# lora_esp.net
KiCad netlist of a schematic drawn in EAGLE
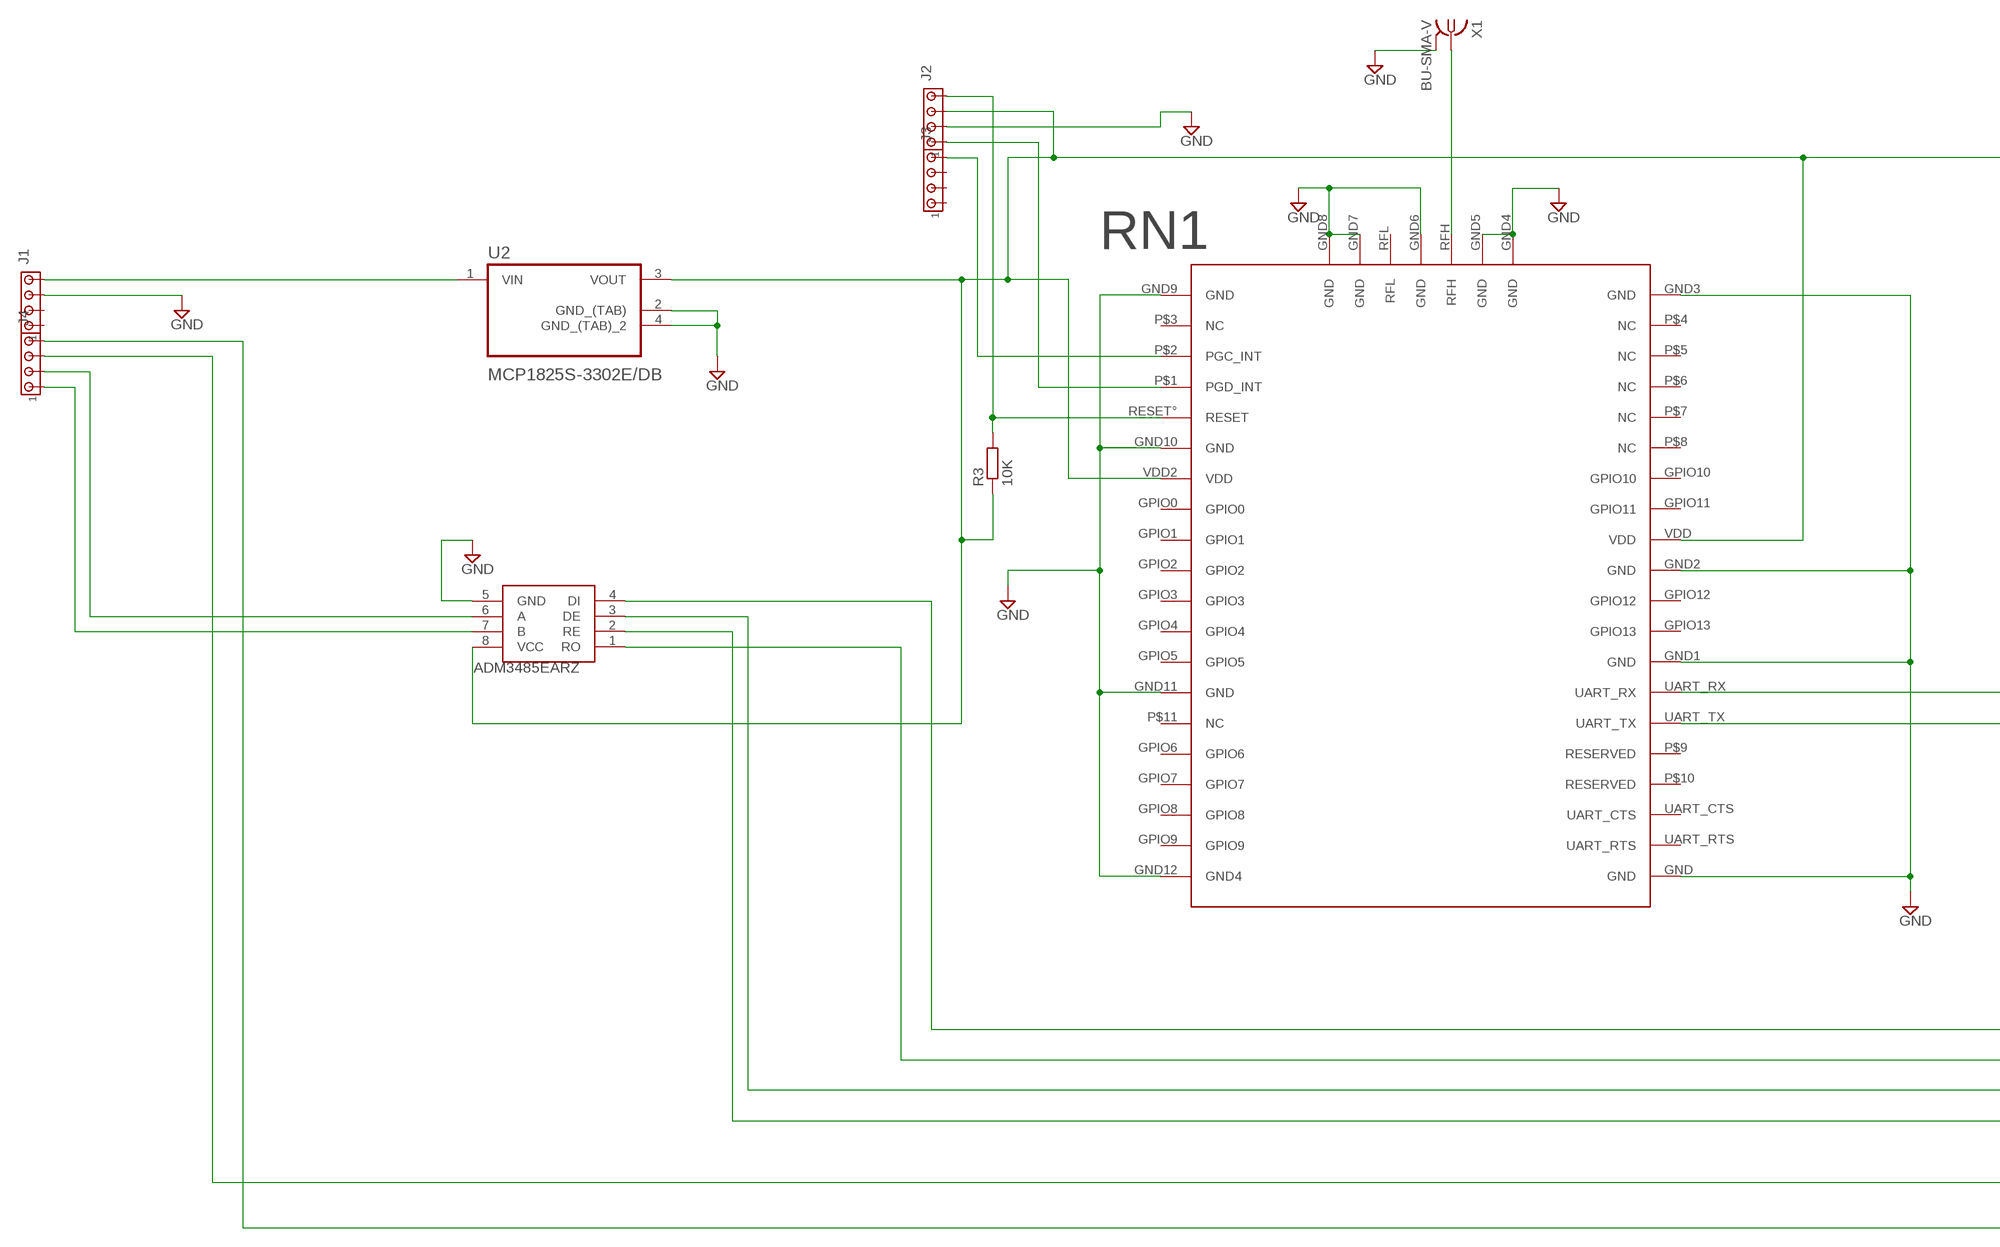
[diagram p0: schematic, sheet 1, part 1 of 2]
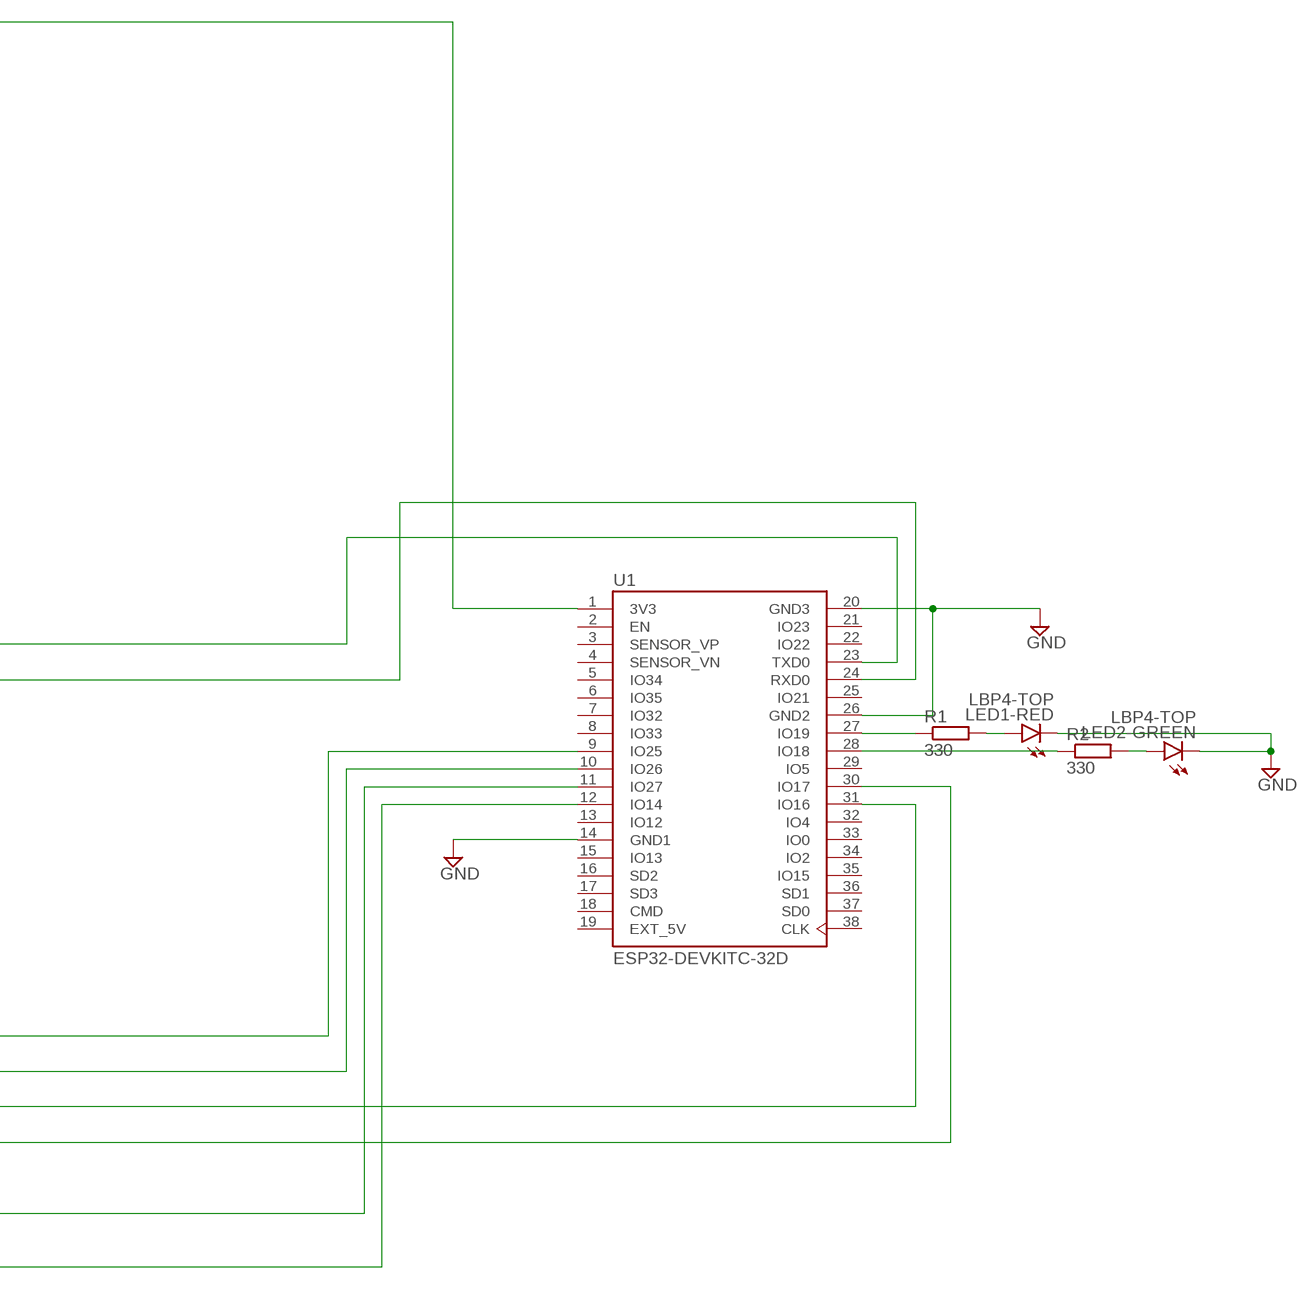
[diagram p1: schematic, sheet 1, part 2 of 2]

(export (version "E")
  (design (tool "Eeschema 10.0.6"))
  (components
    (comp (ref "ADM3485EARZ")
      (value "AMD3485E")
      (footprint "eagle-import:AMD3485E")
      (libsource (lib "eagle-import") (part "AMD3485E"))
    )
    (comp (ref "J1")
      (value "MTA04-100")
      (footprint "eagle-import:10X04MTA")
      (libsource (lib "eagle-import") (part "MTA04-100"))
    )
    (comp (ref "J2")
      (value "MTA04-100")
      (footprint "eagle-import:10X04MTA")
      (libsource (lib "eagle-import") (part "MTA04-100"))
    )
    (comp (ref "J3")
      (value "MTA04-100")
      (footprint "eagle-import:10X04MTA")
      (libsource (lib "eagle-import") (part "MTA04-100"))
    )
    (comp (ref "J4")
      (value "MTA04-100")
      (footprint "eagle-import:10X04MTA")
      (libsource (lib "eagle-import") (part "MTA04-100"))
    )
    (comp (ref "LED1-RED")
      (value "LBP4-TOP")
      (footprint "eagle-import:P47F-TOP")
      (libsource (lib "eagle-import") (part "P4-TOPLB"))
    )
    (comp (ref "LED2-GREEN")
      (value "LBP4-TOP")
      (footprint "eagle-import:P47F-TOP")
      (libsource (lib "eagle-import") (part "P4-TOPLB"))
    )
    (comp (ref "R1")
      (value "330")
      (footprint "eagle-import:0204_5")
      (libsource (lib "eagle-import") (part "R-EU_0204/5"))
    )
    (comp (ref "R2")
      (value "330")
      (footprint "eagle-import:0204_5")
      (libsource (lib "eagle-import") (part "R-EU_0204/5"))
    )
    (comp (ref "R3")
      (value "10K")
      (footprint "eagle-import:0204_5")
      (libsource (lib "eagle-import") (part "R-EU_0204/5"))
    )
    (comp (ref "RN1")
      (value "NEW_RN2483")
      (footprint "eagle-import:NEW_RN2483")
      (libsource (lib "eagle-import") (part "NEW_RN2483"))
    )
    (comp (ref "U1")
      (value "ESP32-DEVKITC-32D")
      (footprint "eagle-import:MODULE_ESP32-DEVKITC-32D")
      (fields (field (name "MF") "Espressif Systems"))
      (libsource (lib "eagle-import") (part "ESP32-DEVKITC-32D"))
    )
    (comp (ref "U2")
      (value "MCP1825S-3302E/DB")
      (footprint "eagle-import:SOT230P700X180-4N")
      (fields (field (name "MF") "Microchip"))
      (libsource (lib "eagle-import") (part "MCP1825S-3302E/DB"))
    )
    (comp (ref "X1")
      (value "BU-SMA-V")
      (footprint "eagle-import:BU-SMA-V")
      (libsource (lib "eagle-import") (part "BU-SMA-V"))
    )
  )
  (nets
    (net (code "1") (name "/EXT_5V") (class "Default")
      (node (ref "U1") (pin "19") (pinfunction "EXT_5V_19") (pintype "power_in"))
    )
    (net (code "2") (name "GND") (class "Default")
      (node (ref "ADM3485EARZ") (pin "5") (pinfunction "GND_5") (pintype "bidirectional"))
      (node (ref "J1") (pin "3") (pinfunction "3_3") (pintype "passive"))
      (node (ref "J2") (pin "2") (pinfunction "2_2") (pintype "passive"))
      (node (ref "LED1-RED") (pin "C") (pinfunction "C_C") (pintype "passive"))
      (node (ref "LED2-GREEN") (pin "C") (pinfunction "C_C") (pintype "passive"))
      (node (ref "RN1") (pin "GND") (pinfunction "GND_GND") (pintype "bidirectional"))
      (node (ref "RN1") (pin "GND1") (pinfunction "GND_GND1") (pintype "bidirectional"))
      (node (ref "RN1") (pin "GND10") (pinfunction "GND_GND10") (pintype "bidirectional"))
      (node (ref "RN1") (pin "GND11") (pinfunction "GND_GND11") (pintype "bidirectional"))
      (node (ref "RN1") (pin "GND12") (pinfunction "GND4_GND12") (pintype "bidirectional"))
      (node (ref "RN1") (pin "GND2") (pinfunction "GND_GND2") (pintype "bidirectional"))
      (node (ref "RN1") (pin "GND3") (pinfunction "GND_GND3") (pintype "bidirectional"))
      (node (ref "RN1") (pin "GND4") (pinfunction "GND_GND4") (pintype "bidirectional"))
      (node (ref "RN1") (pin "GND5") (pinfunction "GND_GND5") (pintype "bidirectional"))
      (node (ref "RN1") (pin "GND6") (pinfunction "GND_GND6") (pintype "bidirectional"))
      (node (ref "RN1") (pin "GND7") (pinfunction "GND_GND7") (pintype "bidirectional"))
      (node (ref "RN1") (pin "GND8") (pinfunction "GND_GND8") (pintype "bidirectional"))
      (node (ref "RN1") (pin "GND9") (pinfunction "GND_GND9") (pintype "bidirectional"))
      (node (ref "U1") (pin "14") (pinfunction "GND1_14") (pintype "power_in"))
      (node (ref "U1") (pin "20") (pinfunction "GND3_20") (pintype "power_in"))
      (node (ref "U1") (pin "26") (pinfunction "GND2_26") (pintype "power_in"))
      (node (ref "U2") (pin "2") (pinfunction "GND_(TAB)_2") (pintype "power_in"))
      (node (ref "U2") (pin "4") (pinfunction "GND_(TAB)_2_4") (pintype "power_in"))
      (node (ref "X1") (pin "2") (pinfunction "2_2") (pintype "passive"))
      (node (ref "X1") (pin "3") (pinfunction "2_3") (pintype "passive"))
      (node (ref "X1") (pin "4") (pinfunction "2_4") (pintype "passive"))
      (node (ref "X1") (pin "5") (pinfunction "2_5") (pintype "passive"))
    )
    (net (code "3") (name "Net-(ADM3485EARZ-A)") (class "Default")
      (node (ref "ADM3485EARZ") (pin "6") (pinfunction "A_6") (pintype "bidirectional"))
      (node (ref "J4") (pin "2") (pinfunction "2_2") (pintype "passive"))
    )
    (net (code "4") (name "Net-(ADM3485EARZ-B)") (class "Default")
      (node (ref "ADM3485EARZ") (pin "7") (pinfunction "B_7") (pintype "bidirectional"))
      (node (ref "J4") (pin "1") (pinfunction "1_1") (pintype "passive"))
    )
    (net (code "5") (name "Net-(ADM3485EARZ-DE)") (class "Default")
      (node (ref "ADM3485EARZ") (pin "3") (pinfunction "DE_3") (pintype "bidirectional"))
      (node (ref "U1") (pin "31") (pinfunction "IO16_31") (pintype "bidirectional"))
    )
    (net (code "6") (name "Net-(ADM3485EARZ-DI)") (class "Default")
      (node (ref "ADM3485EARZ") (pin "4") (pinfunction "DI_4") (pintype "bidirectional"))
      (node (ref "U1") (pin "9") (pinfunction "IO25_9") (pintype "bidirectional"))
    )
    (net (code "7") (name "Net-(ADM3485EARZ-RE)") (class "Default")
      (node (ref "ADM3485EARZ") (pin "2") (pinfunction "RE_2") (pintype "bidirectional"))
      (node (ref "U1") (pin "30") (pinfunction "IO17_30") (pintype "bidirectional"))
    )
    (net (code "8") (name "Net-(ADM3485EARZ-RO)") (class "Default")
      (node (ref "ADM3485EARZ") (pin "1") (pinfunction "RO_1") (pintype "bidirectional"))
      (node (ref "U1") (pin "10") (pinfunction "IO26_10") (pintype "bidirectional"))
    )
    (net (code "9") (name "Net-(ADM3485EARZ-VCC)") (class "Default")
      (node (ref "ADM3485EARZ") (pin "8") (pinfunction "VCC_8") (pintype "bidirectional"))
      (node (ref "J2") (pin "3") (pinfunction "3_3") (pintype "passive"))
      (node (ref "R3") (pin "1") (pinfunction "1_1") (pintype "passive"))
      (node (ref "RN1") (pin "VDD") (pinfunction "VDD_VDD") (pintype "bidirectional"))
      (node (ref "RN1") (pin "VDD2") (pinfunction "VDD_VDD2") (pintype "bidirectional"))
      (node (ref "U1") (pin "1") (pinfunction "3V3_1") (pintype "power_in"))
      (node (ref "U2") (pin "3") (pinfunction "VOUT_3") (pintype "output"))
    )
    (net (code "10") (name "Net-(LED1-RED-PadA)") (class "Default")
      (node (ref "LED1-RED") (pin "A") (pinfunction "A_A") (pintype "passive"))
      (node (ref "R1") (pin "2") (pinfunction "2_2") (pintype "passive"))
    )
    (net (code "11") (name "Net-(LED2-GREEN-PadA)") (class "Default")
      (node (ref "LED2-GREEN") (pin "A") (pinfunction "A_A") (pintype "passive"))
      (node (ref "R2") (pin "2") (pinfunction "2_2") (pintype "passive"))
    )
    (net (code "12") (name "Net-(RN1-PGC_INT)") (class "Default")
      (node (ref "J3") (pin "4") (pinfunction "4_4") (pintype "passive"))
      (node (ref "RN1") (pin "P$2") (pinfunction "PGC_INT_P$2") (pintype "bidirectional"))
    )
    (net (code "13") (name "Net-(RN1-PGD_INT)") (class "Default")
      (node (ref "J2") (pin "1") (pinfunction "1_1") (pintype "passive"))
      (node (ref "RN1") (pin "P$1") (pinfunction "PGD_INT_P$1") (pintype "bidirectional"))
    )
    (net (code "14") (name "Net-(RN1-PadRFH)") (class "Default")
      (node (ref "RN1") (pin "RFH") (pinfunction "RFH_RFH") (pintype "bidirectional"))
      (node (ref "X1") (pin "1") (pinfunction "1_1") (pintype "passive"))
    )
    (net (code "15") (name "Net-(RN1-RESET)") (class "Default")
      (node (ref "J2") (pin "4") (pinfunction "4_4") (pintype "passive"))
      (node (ref "R3") (pin "2") (pinfunction "2_2") (pintype "passive"))
      (node (ref "RN1") (pin "RESET°") (pinfunction "RESET_RESET°") (pintype "bidirectional"))
    )
    (net (code "16") (name "Net-(U1-IO14)") (class "Default")
      (node (ref "J4") (pin "4") (pinfunction "4_4") (pintype "passive"))
      (node (ref "U1") (pin "12") (pinfunction "IO14_12") (pintype "bidirectional"))
    )
    (net (code "17") (name "Net-(U1-IO18)") (class "Default")
      (node (ref "R2") (pin "1") (pinfunction "1_1") (pintype "passive"))
      (node (ref "U1") (pin "28") (pinfunction "IO18_28") (pintype "bidirectional"))
    )
    (net (code "18") (name "Net-(U1-IO19)") (class "Default")
      (node (ref "R1") (pin "1") (pinfunction "1_1") (pintype "passive"))
      (node (ref "U1") (pin "27") (pinfunction "IO19_27") (pintype "bidirectional"))
    )
    (net (code "19") (name "Net-(U1-IO27)") (class "Default")
      (node (ref "J4") (pin "3") (pinfunction "3_3") (pintype "passive"))
      (node (ref "U1") (pin "11") (pinfunction "IO27_11") (pintype "bidirectional"))
    )
    (net (code "20") (name "Net-(U1-RXD0)") (class "Default")
      (node (ref "RN1") (pin "UART_TX") (pinfunction "UART_TX_UART_TX") (pintype "bidirectional"))
      (node (ref "U1") (pin "24") (pinfunction "RXD0_24") (pintype "input"))
    )
    (net (code "21") (name "Net-(U1-TXD0)") (class "Default")
      (node (ref "RN1") (pin "UART_RX") (pinfunction "UART_RX_UART_RX") (pintype "bidirectional"))
      (node (ref "U1") (pin "23") (pinfunction "TXD0_23") (pintype "output"))
    )
    (net (code "22") (name "Net-(U2-VIN)") (class "Default")
      (node (ref "J1") (pin "4") (pinfunction "4_4") (pintype "passive"))
      (node (ref "U2") (pin "1") (pinfunction "VIN_1") (pintype "input"))
    )
    (net (code "23") (name "unconnected-(J1-Pad1)") (class "Default")
      (node (ref "J1") (pin "1") (pinfunction "1_1") (pintype "passive"))
    )
    (net (code "24") (name "unconnected-(J1-Pad2)") (class "Default")
      (node (ref "J1") (pin "2") (pinfunction "2_2") (pintype "passive"))
    )
    (net (code "25") (name "unconnected-(J3-Pad1)") (class "Default")
      (node (ref "J3") (pin "1") (pinfunction "1_1") (pintype "passive"))
    )
    (net (code "26") (name "unconnected-(J3-Pad2)") (class "Default")
      (node (ref "J3") (pin "2") (pinfunction "2_2") (pintype "passive"))
    )
    (net (code "27") (name "unconnected-(J3-Pad3)") (class "Default")
      (node (ref "J3") (pin "3") (pinfunction "3_3") (pintype "passive"))
    )
    (net (code "28") (name "unconnected-(RN1-NC-PadP$3)") (class "Default")
      (node (ref "RN1") (pin "P$3") (pinfunction "NC_P$3") (pintype "bidirectional"))
    )
    (net (code "29") (name "unconnected-(RN1-NC-PadP$4)") (class "Default")
      (node (ref "RN1") (pin "P$4") (pinfunction "NC_P$4") (pintype "bidirectional"))
    )
    (net (code "30") (name "unconnected-(RN1-NC-PadP$5)") (class "Default")
      (node (ref "RN1") (pin "P$5") (pinfunction "NC_P$5") (pintype "bidirectional"))
    )
    (net (code "31") (name "unconnected-(RN1-NC-PadP$6)") (class "Default")
      (node (ref "RN1") (pin "P$6") (pinfunction "NC_P$6") (pintype "bidirectional"))
    )
    (net (code "32") (name "unconnected-(RN1-NC-PadP$7)") (class "Default")
      (node (ref "RN1") (pin "P$7") (pinfunction "NC_P$7") (pintype "bidirectional"))
    )
    (net (code "33") (name "unconnected-(RN1-NC-PadP$8)") (class "Default")
      (node (ref "RN1") (pin "P$8") (pinfunction "NC_P$8") (pintype "bidirectional"))
    )
    (net (code "34") (name "unconnected-(RN1-NC-PadP$11)") (class "Default")
      (node (ref "RN1") (pin "P$11") (pinfunction "NC_P$11") (pintype "bidirectional"))
    )
    (net (code "35") (name "unconnected-(RN1-PadGPIO0)") (class "Default")
      (node (ref "RN1") (pin "GPIO0") (pinfunction "GPIO0_GPIO0") (pintype "bidirectional"))
    )
    (net (code "36") (name "unconnected-(RN1-PadGPIO1)") (class "Default")
      (node (ref "RN1") (pin "GPIO1") (pinfunction "GPIO1_GPIO1") (pintype "bidirectional"))
    )
    (net (code "37") (name "unconnected-(RN1-PadGPIO2)") (class "Default")
      (node (ref "RN1") (pin "GPIO2") (pinfunction "GPIO2_GPIO2") (pintype "bidirectional"))
    )
    (net (code "38") (name "unconnected-(RN1-PadGPIO3)") (class "Default")
      (node (ref "RN1") (pin "GPIO3") (pinfunction "GPIO3_GPIO3") (pintype "bidirectional"))
    )
    (net (code "39") (name "unconnected-(RN1-PadGPIO4)") (class "Default")
      (node (ref "RN1") (pin "GPIO4") (pinfunction "GPIO4_GPIO4") (pintype "bidirectional"))
    )
    (net (code "40") (name "unconnected-(RN1-PadGPIO5)") (class "Default")
      (node (ref "RN1") (pin "GPIO5") (pinfunction "GPIO5_GPIO5") (pintype "bidirectional"))
    )
    (net (code "41") (name "unconnected-(RN1-PadGPIO6)") (class "Default")
      (node (ref "RN1") (pin "GPIO6") (pinfunction "GPIO6_GPIO6") (pintype "bidirectional"))
    )
    (net (code "42") (name "unconnected-(RN1-PadGPIO7)") (class "Default")
      (node (ref "RN1") (pin "GPIO7") (pinfunction "GPIO7_GPIO7") (pintype "bidirectional"))
    )
    (net (code "43") (name "unconnected-(RN1-PadGPIO8)") (class "Default")
      (node (ref "RN1") (pin "GPIO8") (pinfunction "GPIO8_GPIO8") (pintype "bidirectional"))
    )
    (net (code "44") (name "unconnected-(RN1-PadGPIO9)") (class "Default")
      (node (ref "RN1") (pin "GPIO9") (pinfunction "GPIO9_GPIO9") (pintype "bidirectional"))
    )
    (net (code "45") (name "unconnected-(RN1-PadGPIO10)") (class "Default")
      (node (ref "RN1") (pin "GPIO10") (pinfunction "GPIO10_GPIO10") (pintype "bidirectional"))
    )
    (net (code "46") (name "unconnected-(RN1-PadGPIO11)") (class "Default")
      (node (ref "RN1") (pin "GPIO11") (pinfunction "GPIO11_GPIO11") (pintype "bidirectional"))
    )
    (net (code "47") (name "unconnected-(RN1-PadGPIO12)") (class "Default")
      (node (ref "RN1") (pin "GPIO12") (pinfunction "GPIO12_GPIO12") (pintype "bidirectional"))
    )
    (net (code "48") (name "unconnected-(RN1-PadGPIO13)") (class "Default")
      (node (ref "RN1") (pin "GPIO13") (pinfunction "GPIO13_GPIO13") (pintype "bidirectional"))
    )
    (net (code "49") (name "unconnected-(RN1-PadRFL)") (class "Default")
      (node (ref "RN1") (pin "RFL") (pinfunction "RFL_RFL") (pintype "bidirectional"))
    )
    (net (code "50") (name "unconnected-(RN1-PadUART_CTS)") (class "Default")
      (node (ref "RN1") (pin "UART_CTS") (pinfunction "UART_CTS_UART_CTS") (pintype "bidirectional"))
    )
    (net (code "51") (name "unconnected-(RN1-PadUART_RTS)") (class "Default")
      (node (ref "RN1") (pin "UART_RTS") (pinfunction "UART_RTS_UART_RTS") (pintype "bidirectional"))
    )
    (net (code "52") (name "unconnected-(RN1-RESERVED-PadP$9)") (class "Default")
      (node (ref "RN1") (pin "P$9") (pinfunction "RESERVED_P$9") (pintype "bidirectional"))
    )
    (net (code "53") (name "unconnected-(RN1-RESERVED-PadP$10)") (class "Default")
      (node (ref "RN1") (pin "P$10") (pinfunction "RESERVED_P$10") (pintype "bidirectional"))
    )
    (net (code "54") (name "unconnected-(U1-CLK-Pad38)") (class "Default")
      (node (ref "U1") (pin "38") (pinfunction "CLK_38") (pintype "input"))
    )
    (net (code "55") (name "unconnected-(U1-CMD-Pad18)") (class "Default")
      (node (ref "U1") (pin "18") (pinfunction "CMD_18") (pintype "bidirectional"))
    )
    (net (code "56") (name "unconnected-(U1-EN-Pad2)") (class "Default")
      (node (ref "U1") (pin "2") (pinfunction "EN_2") (pintype "input"))
    )
    (net (code "57") (name "unconnected-(U1-IO0-Pad33)") (class "Default")
      (node (ref "U1") (pin "33") (pinfunction "IO0_33") (pintype "bidirectional"))
    )
    (net (code "58") (name "unconnected-(U1-IO2-Pad34)") (class "Default")
      (node (ref "U1") (pin "34") (pinfunction "IO2_34") (pintype "bidirectional"))
    )
    (net (code "59") (name "unconnected-(U1-IO4-Pad32)") (class "Default")
      (node (ref "U1") (pin "32") (pinfunction "IO4_32") (pintype "bidirectional"))
    )
    (net (code "60") (name "unconnected-(U1-IO5-Pad29)") (class "Default")
      (node (ref "U1") (pin "29") (pinfunction "IO5_29") (pintype "bidirectional"))
    )
    (net (code "61") (name "unconnected-(U1-IO12-Pad13)") (class "Default")
      (node (ref "U1") (pin "13") (pinfunction "IO12_13") (pintype "bidirectional"))
    )
    (net (code "62") (name "unconnected-(U1-IO13-Pad15)") (class "Default")
      (node (ref "U1") (pin "15") (pinfunction "IO13_15") (pintype "bidirectional"))
    )
    (net (code "63") (name "unconnected-(U1-IO15-Pad35)") (class "Default")
      (node (ref "U1") (pin "35") (pinfunction "IO15_35") (pintype "bidirectional"))
    )
    (net (code "64") (name "unconnected-(U1-IO21-Pad25)") (class "Default")
      (node (ref "U1") (pin "25") (pinfunction "IO21_25") (pintype "bidirectional"))
    )
    (net (code "65") (name "unconnected-(U1-IO22-Pad22)") (class "Default")
      (node (ref "U1") (pin "22") (pinfunction "IO22_22") (pintype "bidirectional"))
    )
    (net (code "66") (name "unconnected-(U1-IO23-Pad21)") (class "Default")
      (node (ref "U1") (pin "21") (pinfunction "IO23_21") (pintype "bidirectional"))
    )
    (net (code "67") (name "unconnected-(U1-IO32-Pad7)") (class "Default")
      (node (ref "U1") (pin "7") (pinfunction "IO32_7") (pintype "bidirectional"))
    )
    (net (code "68") (name "unconnected-(U1-IO33-Pad8)") (class "Default")
      (node (ref "U1") (pin "8") (pinfunction "IO33_8") (pintype "bidirectional"))
    )
    (net (code "69") (name "unconnected-(U1-IO34-Pad5)") (class "Default")
      (node (ref "U1") (pin "5") (pinfunction "IO34_5") (pintype "bidirectional"))
    )
    (net (code "70") (name "unconnected-(U1-IO35-Pad6)") (class "Default")
      (node (ref "U1") (pin "6") (pinfunction "IO35_6") (pintype "bidirectional"))
    )
    (net (code "71") (name "unconnected-(U1-SD0-Pad37)") (class "Default")
      (node (ref "U1") (pin "37") (pinfunction "SD0_37") (pintype "bidirectional"))
    )
    (net (code "72") (name "unconnected-(U1-SD1-Pad36)") (class "Default")
      (node (ref "U1") (pin "36") (pinfunction "SD1_36") (pintype "bidirectional"))
    )
    (net (code "73") (name "unconnected-(U1-SD2-Pad16)") (class "Default")
      (node (ref "U1") (pin "16") (pinfunction "SD2_16") (pintype "bidirectional"))
    )
    (net (code "74") (name "unconnected-(U1-SD3-Pad17)") (class "Default")
      (node (ref "U1") (pin "17") (pinfunction "SD3_17") (pintype "bidirectional"))
    )
    (net (code "75") (name "unconnected-(U1-SENSOR_VN-Pad4)") (class "Default")
      (node (ref "U1") (pin "4") (pinfunction "SENSOR_VN_4") (pintype "input"))
    )
    (net (code "76") (name "unconnected-(U1-SENSOR_VP-Pad3)") (class "Default")
      (node (ref "U1") (pin "3") (pinfunction "SENSOR_VP_3") (pintype "input"))
    )
  )
)
